# Net2CPC.net
KiCad netlist of a schematic drawn in EAGLE
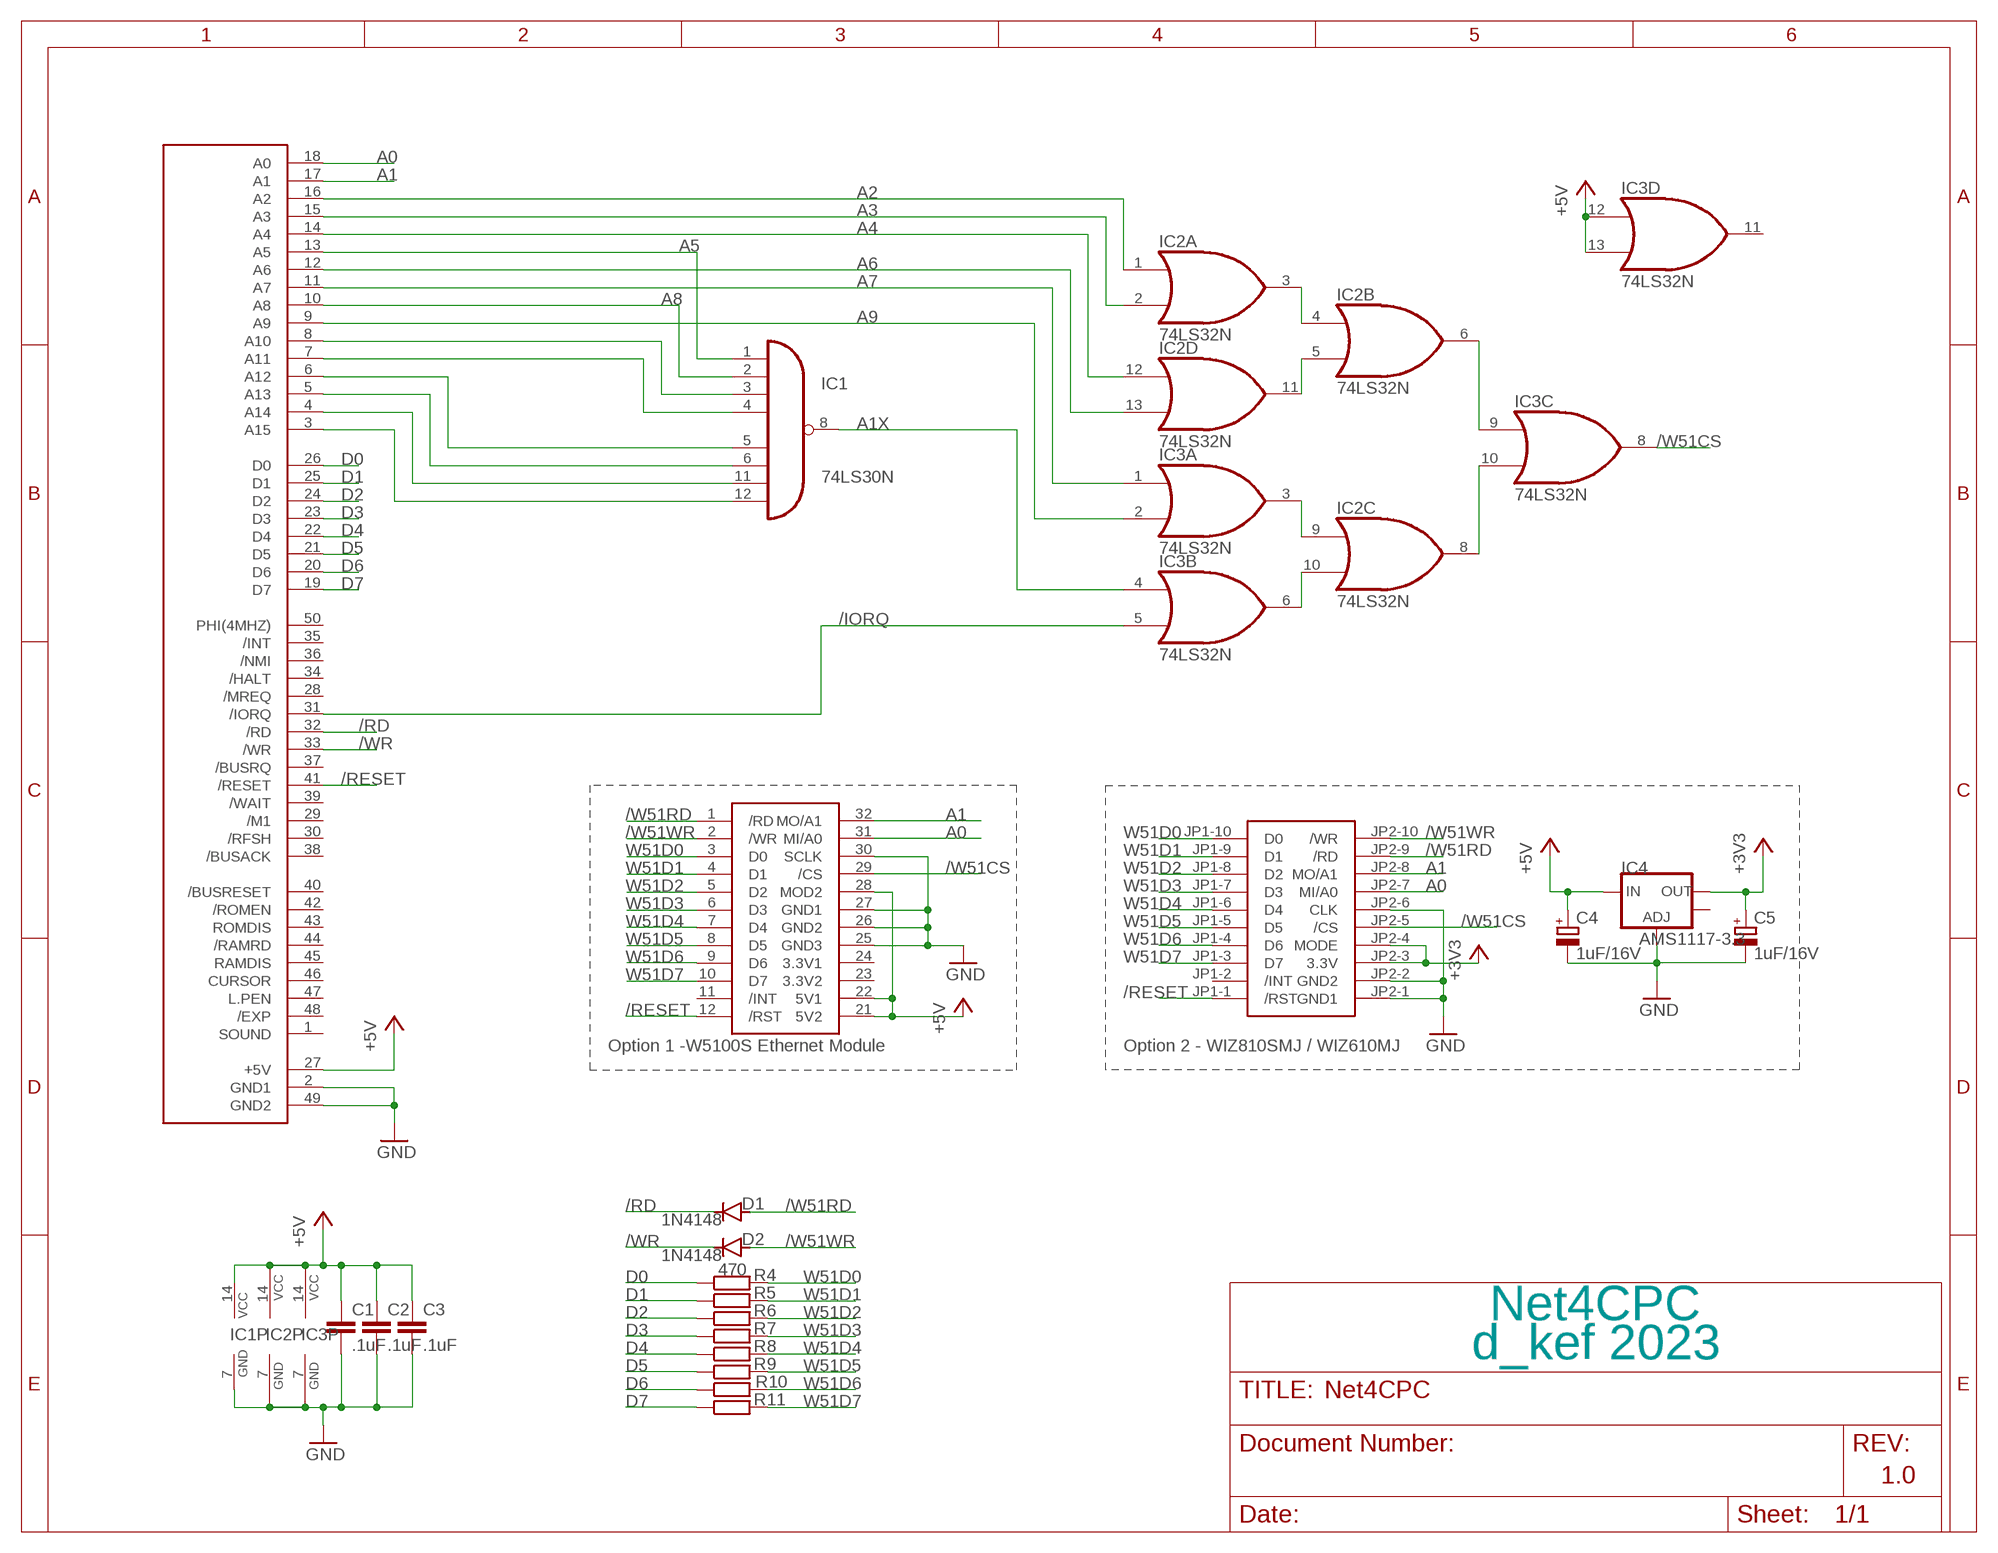
[diagram p0: schematic, sheet 1]

(export (version "E")
  (design (tool "Eeschema 10.0.6"))
  (components
    (comp (ref "C1")
      (value ".1uF")
      (footprint "eagle-import:C025-025X050")
      (libsource (lib "eagle-import") (part "C-EU025-025X050"))
    )
    (comp (ref "C2")
      (value ".1uF")
      (footprint "eagle-import:C025-025X050")
      (libsource (lib "eagle-import") (part "C-EU025-025X050"))
    )
    (comp (ref "C3")
      (value ".1uF")
      (footprint "eagle-import:C025-025X050")
      (libsource (lib "eagle-import") (part "C-EU025-025X050"))
    )
    (comp (ref "C4")
      (value "1uF/16V")
      (footprint "eagle-import:E5-6")
      (libsource (lib "eagle-import") (part "CPOL-EUE5-6"))
    )
    (comp (ref "C5")
      (value "1uF/16V")
      (footprint "eagle-import:E5-6")
      (libsource (lib "eagle-import") (part "CPOL-EUE5-6"))
    )
    (comp (ref "CON1")
      (value "CPCBUS")
      (footprint "eagle-import:2X25")
      (libsource (lib "eagle-import") (part "AMSTRAD_CPC_BUSP"))
    )
    (comp (ref "D1")
      (value "1N4148")
      (footprint "eagle-import:DO35-7")
      (libsource (lib "eagle-import") (part "1N4148DO35-7"))
    )
    (comp (ref "D2")
      (value "1N4148")
      (footprint "eagle-import:DO35-7")
      (libsource (lib "eagle-import") (part "1N4148DO35-7"))
    )
    (comp (ref "IC1")
      (value "74LS30N")
      (footprint "eagle-import:DIL14")
      (libsource (lib "eagle-import") (part "7430NHCT"))
    )
    (comp (ref "IC2")
      (value "74LS32N")
      (footprint "eagle-import:DIL14")
      (libsource (lib "eagle-import") (part "7432NLS"))
    )
    (comp (ref "IC3")
      (value "74LS32N")
      (footprint "eagle-import:DIL14")
      (libsource (lib "eagle-import") (part "7432NLS"))
    )
    (comp (ref "IC4")
      (value "AMS1117-3.3")
      (footprint "eagle-import:SOT223")
      (libsource (lib "eagle-import") (part "V_REG_LM1117SOT223"))
    )
    (comp (ref "R4")
      (value "470")
      (footprint "eagle-import:0204_7")
      (libsource (lib "eagle-import") (part "R-EU_0204/7"))
    )
    (comp (ref "R5")
      (value "470")
      (footprint "eagle-import:0204_7")
      (libsource (lib "eagle-import") (part "R-EU_0204/7"))
    )
    (comp (ref "R6")
      (value "470")
      (footprint "eagle-import:0204_7")
      (libsource (lib "eagle-import") (part "R-EU_0204/7"))
    )
    (comp (ref "R7")
      (value "470")
      (footprint "eagle-import:0204_7")
      (libsource (lib "eagle-import") (part "R-EU_0204/7"))
    )
    (comp (ref "R8")
      (value "470")
      (footprint "eagle-import:0204_7")
      (libsource (lib "eagle-import") (part "R-EU_0204/7"))
    )
    (comp (ref "R9")
      (value "470")
      (footprint "eagle-import:0204_7")
      (libsource (lib "eagle-import") (part "R-EU_0204/7"))
    )
    (comp (ref "R10")
      (value "470")
      (footprint "eagle-import:0204_7")
      (libsource (lib "eagle-import") (part "R-EU_0204/7"))
    )
    (comp (ref "R11")
      (value "470")
      (footprint "eagle-import:0204_7")
      (libsource (lib "eagle-import") (part "R-EU_0204/7"))
    )
    (comp (ref "W5100S-MODULE")
      (value "W5100S-NETWORK-MODULENO-NAMES")
      (footprint "eagle-import:W5100S-NETWORK-MODULE-NO-NAMES")
      (libsource (lib "eagle-import") (part "W5100S-NETWORK-MODULENO-NAMES"))
    )
    (comp (ref "WIZ810SMJ")
      (value "WIZ810SMJ-NETWORK-MODULENO-NAMES")
      (footprint "eagle-import:WIZ810SMJ-NETWORK-MODULE-NO-NAMES")
      (libsource (lib "eagle-import") (part "WIZ810SMJ-NETWORK-MODULENO-NAMES"))
    )
  )
  (nets
    (net (code "1") (name "+3V3") (class "Default")
      (node (ref "C5") (pin "+") (pinfunction "+_+") (pintype "passive"))
      (node (ref "IC4") (pin "2") (pinfunction "OUT_2") (pintype "output"))
      (node (ref "WIZ810SMJ") (pin "JP2-3") (pinfunction "3.3V_JP2-3") (pintype "power_in"))
      (node (ref "WIZ810SMJ") (pin "JP2-4") (pinfunction "MODE_JP2-4") (pintype "passive"))
    )
    (net (code "2") (name "+5V") (class "Default")
      (node (ref "C1") (pin "1") (pinfunction "1_1") (pintype "passive"))
      (node (ref "C2") (pin "1") (pinfunction "1_1") (pintype "passive"))
      (node (ref "C3") (pin "1") (pinfunction "1_1") (pintype "passive"))
      (node (ref "C4") (pin "+") (pinfunction "+_+") (pintype "passive"))
      (node (ref "CON1") (pin "27") (pinfunction "+5V_27") (pintype "bidirectional"))
      (node (ref "IC1") (pin "14") (pinfunction "VCC_14") (pintype "power_in"))
      (node (ref "IC2") (pin "14") (pinfunction "VCC_14") (pintype "power_in"))
      (node (ref "IC3") (pin "12") (pinfunction "I0_12") (pintype "input"))
      (node (ref "IC3") (pin "13") (pinfunction "I1_13") (pintype "input"))
      (node (ref "IC3") (pin "14") (pinfunction "VCC_14") (pintype "power_in"))
      (node (ref "IC4") (pin "3") (pinfunction "IN_3") (pintype "input"))
      (node (ref "W5100S-MODULE") (pin "21") (pinfunction "5V2_21") (pintype "power_in"))
      (node (ref "W5100S-MODULE") (pin "22") (pinfunction "5V1_22") (pintype "power_in"))
      (node (ref "W5100S-MODULE") (pin "28") (pinfunction "MOD2_28") (pintype "passive"))
    )
    (net (code "3") (name "/3.3V1") (class "Default")
      (node (ref "W5100S-MODULE") (pin "24") (pinfunction "3.3V1_24") (pintype "power_in"))
    )
    (net (code "4") (name "/3.3V2") (class "Default")
      (node (ref "W5100S-MODULE") (pin "23") (pinfunction "3.3V2_23") (pintype "power_in"))
    )
    (net (code "5") (name "/A0") (class "Default")
      (node (ref "CON1") (pin "18") (pinfunction "A0_18") (pintype "bidirectional"))
      (node (ref "W5100S-MODULE") (pin "31") (pinfunction "MI/A0_31") (pintype "input"))
      (node (ref "WIZ810SMJ") (pin "JP2-7") (pinfunction "MI/A0_JP2-7") (pintype "input"))
    )
    (net (code "6") (name "/A1") (class "Default")
      (node (ref "CON1") (pin "17") (pinfunction "A1_17") (pintype "bidirectional"))
      (node (ref "W5100S-MODULE") (pin "32") (pinfunction "MO/A1_32") (pintype "bidirectional"))
      (node (ref "WIZ810SMJ") (pin "JP2-8") (pinfunction "MO/A1_JP2-8") (pintype "bidirectional"))
    )
    (net (code "7") (name "/A1X") (class "Default")
      (node (ref "IC1") (pin "8") (pinfunction "O_8") (pintype "output"))
      (node (ref "IC3") (pin "4") (pinfunction "I0_4") (pintype "input"))
    )
    (net (code "8") (name "/A2") (class "Default")
      (node (ref "CON1") (pin "16") (pinfunction "A2_16") (pintype "bidirectional"))
      (node (ref "IC2") (pin "1") (pinfunction "I0_1") (pintype "input"))
    )
    (net (code "9") (name "/A3") (class "Default")
      (node (ref "CON1") (pin "15") (pinfunction "A3_15") (pintype "bidirectional"))
      (node (ref "IC2") (pin "2") (pinfunction "I1_2") (pintype "input"))
    )
    (net (code "10") (name "/A4") (class "Default")
      (node (ref "CON1") (pin "14") (pinfunction "A4_14") (pintype "bidirectional"))
      (node (ref "IC2") (pin "12") (pinfunction "I0_12") (pintype "input"))
    )
    (net (code "11") (name "/A5") (class "Default")
      (node (ref "CON1") (pin "13") (pinfunction "A5_13") (pintype "bidirectional"))
      (node (ref "IC1") (pin "1") (pinfunction "I0_1") (pintype "input"))
    )
    (net (code "12") (name "/A6") (class "Default")
      (node (ref "CON1") (pin "12") (pinfunction "A6_12") (pintype "bidirectional"))
      (node (ref "IC2") (pin "13") (pinfunction "I1_13") (pintype "input"))
    )
    (net (code "13") (name "/A7") (class "Default")
      (node (ref "CON1") (pin "11") (pinfunction "A7_11") (pintype "bidirectional"))
      (node (ref "IC3") (pin "1") (pinfunction "I0_1") (pintype "input"))
    )
    (net (code "14") (name "/A8") (class "Default")
      (node (ref "CON1") (pin "10") (pinfunction "A8_10") (pintype "bidirectional"))
      (node (ref "IC1") (pin "2") (pinfunction "I1_2") (pintype "input"))
    )
    (net (code "15") (name "/A9") (class "Default")
      (node (ref "CON1") (pin "9") (pinfunction "A9_9") (pintype "bidirectional"))
      (node (ref "IC3") (pin "2") (pinfunction "I1_2") (pintype "input"))
    )
    (net (code "16") (name "/D0") (class "Default")
      (node (ref "CON1") (pin "26") (pinfunction "D0_26") (pintype "bidirectional"))
      (node (ref "R4") (pin "1") (pinfunction "1_1") (pintype "passive"))
    )
    (net (code "17") (name "/D1") (class "Default")
      (node (ref "CON1") (pin "25") (pinfunction "D1_25") (pintype "bidirectional"))
      (node (ref "R5") (pin "1") (pinfunction "1_1") (pintype "passive"))
    )
    (net (code "18") (name "/D2") (class "Default")
      (node (ref "CON1") (pin "24") (pinfunction "D2_24") (pintype "bidirectional"))
      (node (ref "R6") (pin "1") (pinfunction "1_1") (pintype "passive"))
    )
    (net (code "19") (name "/D3") (class "Default")
      (node (ref "CON1") (pin "23") (pinfunction "D3_23") (pintype "bidirectional"))
      (node (ref "R7") (pin "1") (pinfunction "1_1") (pintype "passive"))
    )
    (net (code "20") (name "/D4") (class "Default")
      (node (ref "CON1") (pin "22") (pinfunction "D4_22") (pintype "bidirectional"))
      (node (ref "R8") (pin "1") (pinfunction "1_1") (pintype "passive"))
    )
    (net (code "21") (name "/D5") (class "Default")
      (node (ref "CON1") (pin "21") (pinfunction "D5_21") (pintype "bidirectional"))
      (node (ref "R9") (pin "1") (pinfunction "1_1") (pintype "passive"))
    )
    (net (code "22") (name "/D6") (class "Default")
      (node (ref "CON1") (pin "20") (pinfunction "D6_20") (pintype "bidirectional"))
      (node (ref "R10") (pin "1") (pinfunction "1_1") (pintype "passive"))
    )
    (net (code "23") (name "/D7") (class "Default")
      (node (ref "CON1") (pin "19") (pinfunction "D7_19") (pintype "bidirectional"))
      (node (ref "R11") (pin "1") (pinfunction "1_1") (pintype "passive"))
    )
    (net (code "24") (name "/W51D0") (class "Default")
      (node (ref "R4") (pin "2") (pinfunction "2_2") (pintype "passive"))
      (node (ref "W5100S-MODULE") (pin "3") (pinfunction "D0_3") (pintype "bidirectional"))
      (node (ref "WIZ810SMJ") (pin "JP1-10") (pinfunction "D0_JP1-10") (pintype "bidirectional"))
    )
    (net (code "25") (name "/W51D1") (class "Default")
      (node (ref "R5") (pin "2") (pinfunction "2_2") (pintype "passive"))
      (node (ref "W5100S-MODULE") (pin "4") (pinfunction "D1_4") (pintype "bidirectional"))
      (node (ref "WIZ810SMJ") (pin "JP1-9") (pinfunction "D1_JP1-9") (pintype "bidirectional"))
    )
    (net (code "26") (name "/W51D2") (class "Default")
      (node (ref "R6") (pin "2") (pinfunction "2_2") (pintype "passive"))
      (node (ref "W5100S-MODULE") (pin "5") (pinfunction "D2_5") (pintype "bidirectional"))
      (node (ref "WIZ810SMJ") (pin "JP1-8") (pinfunction "D2_JP1-8") (pintype "bidirectional"))
    )
    (net (code "27") (name "/W51D3") (class "Default")
      (node (ref "R7") (pin "2") (pinfunction "2_2") (pintype "passive"))
      (node (ref "W5100S-MODULE") (pin "6") (pinfunction "D3_6") (pintype "bidirectional"))
      (node (ref "WIZ810SMJ") (pin "JP1-7") (pinfunction "D3_JP1-7") (pintype "bidirectional"))
    )
    (net (code "28") (name "/W51D4") (class "Default")
      (node (ref "R8") (pin "2") (pinfunction "2_2") (pintype "passive"))
      (node (ref "W5100S-MODULE") (pin "7") (pinfunction "D4_7") (pintype "bidirectional"))
      (node (ref "WIZ810SMJ") (pin "JP1-6") (pinfunction "D4_JP1-6") (pintype "bidirectional"))
    )
    (net (code "29") (name "/W51D5") (class "Default")
      (node (ref "R9") (pin "2") (pinfunction "2_2") (pintype "passive"))
      (node (ref "W5100S-MODULE") (pin "8") (pinfunction "D5_8") (pintype "bidirectional"))
      (node (ref "WIZ810SMJ") (pin "JP1-5") (pinfunction "D5_JP1-5") (pintype "bidirectional"))
    )
    (net (code "30") (name "/W51D6") (class "Default")
      (node (ref "R10") (pin "2") (pinfunction "2_2") (pintype "passive"))
      (node (ref "W5100S-MODULE") (pin "9") (pinfunction "D6_9") (pintype "bidirectional"))
      (node (ref "WIZ810SMJ") (pin "JP1-4") (pinfunction "D6_JP1-4") (pintype "bidirectional"))
    )
    (net (code "31") (name "/W51D7") (class "Default")
      (node (ref "R11") (pin "2") (pinfunction "2_2") (pintype "passive"))
      (node (ref "W5100S-MODULE") (pin "10") (pinfunction "D7_10") (pintype "bidirectional"))
      (node (ref "WIZ810SMJ") (pin "JP1-3") (pinfunction "D7_JP1-3") (pintype "bidirectional"))
    )
    (net (code "32") (name "/{slash}IORQ") (class "Default")
      (node (ref "CON1") (pin "31") (pinfunction "/IORQ_31") (pintype "bidirectional"))
      (node (ref "IC3") (pin "5") (pinfunction "I1_5") (pintype "input"))
    )
    (net (code "33") (name "/{slash}RD") (class "Default")
      (node (ref "CON1") (pin "32") (pinfunction "/RD_32") (pintype "bidirectional"))
      (node (ref "D1") (pin "C") (pinfunction "C_C") (pintype "passive"))
    )
    (net (code "34") (name "/{slash}RESET") (class "Default")
      (node (ref "CON1") (pin "41") (pinfunction "/RESET_41") (pintype "bidirectional"))
      (node (ref "W5100S-MODULE") (pin "12") (pinfunction "/RST_12") (pintype "input"))
      (node (ref "WIZ810SMJ") (pin "JP1-1") (pinfunction "/RST_JP1-1") (pintype "input"))
    )
    (net (code "35") (name "/{slash}W51CS") (class "Default")
      (node (ref "IC3") (pin "8") (pinfunction "O_8") (pintype "output"))
      (node (ref "W5100S-MODULE") (pin "29") (pinfunction "/CS_29") (pintype "input"))
      (node (ref "WIZ810SMJ") (pin "JP2-5") (pinfunction "/CS_JP2-5") (pintype "input"))
    )
    (net (code "36") (name "/{slash}W51RD") (class "Default")
      (node (ref "D1") (pin "A") (pinfunction "A_A") (pintype "passive"))
      (node (ref "W5100S-MODULE") (pin "1") (pinfunction "/RD_1") (pintype "input"))
      (node (ref "WIZ810SMJ") (pin "JP2-9") (pinfunction "/RD_JP2-9") (pintype "input"))
    )
    (net (code "37") (name "/{slash}W51WR") (class "Default")
      (node (ref "D2") (pin "A") (pinfunction "A_A") (pintype "passive"))
      (node (ref "W5100S-MODULE") (pin "2") (pinfunction "/WR_2") (pintype "input"))
      (node (ref "WIZ810SMJ") (pin "JP2-10") (pinfunction "/WR_JP2-10") (pintype "input"))
    )
    (net (code "38") (name "/{slash}WR") (class "Default")
      (node (ref "CON1") (pin "33") (pinfunction "/WR_33") (pintype "bidirectional"))
      (node (ref "D2") (pin "C") (pinfunction "C_C") (pintype "passive"))
    )
    (net (code "39") (name "GND") (class "Default")
      (node (ref "C1") (pin "2") (pinfunction "2_2") (pintype "passive"))
      (node (ref "C2") (pin "2") (pinfunction "2_2") (pintype "passive"))
      (node (ref "C3") (pin "2") (pinfunction "2_2") (pintype "passive"))
      (node (ref "C4") (pin "-") (pinfunction "-_-") (pintype "passive"))
      (node (ref "C5") (pin "-") (pinfunction "-_-") (pintype "passive"))
      (node (ref "CON1") (pin "2") (pinfunction "GND1_2") (pintype "bidirectional"))
      (node (ref "CON1") (pin "49") (pinfunction "GND2_49") (pintype "bidirectional"))
      (node (ref "IC1") (pin "7") (pinfunction "GND_7") (pintype "power_in"))
      (node (ref "IC2") (pin "7") (pinfunction "GND_7") (pintype "power_in"))
      (node (ref "IC3") (pin "7") (pinfunction "GND_7") (pintype "power_in"))
      (node (ref "IC4") (pin "1") (pinfunction "ADJ_1") (pintype "input"))
      (node (ref "W5100S-MODULE") (pin "25") (pinfunction "GND3_25") (pintype "power_in"))
      (node (ref "W5100S-MODULE") (pin "26") (pinfunction "GND2_26") (pintype "power_in"))
      (node (ref "W5100S-MODULE") (pin "27") (pinfunction "GND1_27") (pintype "power_in"))
      (node (ref "W5100S-MODULE") (pin "30") (pinfunction "SCLK_30") (pintype "output"))
      (node (ref "WIZ810SMJ") (pin "JP2-1") (pinfunction "GND1_JP2-1") (pintype "power_in"))
      (node (ref "WIZ810SMJ") (pin "JP2-2") (pinfunction "GND2_JP2-2") (pintype "power_in"))
      (node (ref "WIZ810SMJ") (pin "JP2-6") (pinfunction "CLK_JP2-6") (pintype "output"))
    )
    (net (code "40") (name "Net-(CON1-A10)") (class "Default")
      (node (ref "CON1") (pin "8") (pinfunction "A10_8") (pintype "bidirectional"))
      (node (ref "IC1") (pin "3") (pinfunction "I2_3") (pintype "input"))
    )
    (net (code "41") (name "Net-(CON1-A11)") (class "Default")
      (node (ref "CON1") (pin "7") (pinfunction "A11_7") (pintype "bidirectional"))
      (node (ref "IC1") (pin "4") (pinfunction "I3_4") (pintype "input"))
    )
    (net (code "42") (name "Net-(CON1-A12)") (class "Default")
      (node (ref "CON1") (pin "6") (pinfunction "A12_6") (pintype "bidirectional"))
      (node (ref "IC1") (pin "5") (pinfunction "I4_5") (pintype "input"))
    )
    (net (code "43") (name "Net-(CON1-A13)") (class "Default")
      (node (ref "CON1") (pin "5") (pinfunction "A13_5") (pintype "bidirectional"))
      (node (ref "IC1") (pin "6") (pinfunction "I5_6") (pintype "input"))
    )
    (net (code "44") (name "Net-(CON1-A14)") (class "Default")
      (node (ref "CON1") (pin "4") (pinfunction "A14_4") (pintype "bidirectional"))
      (node (ref "IC1") (pin "11") (pinfunction "I6_11") (pintype "input"))
    )
    (net (code "45") (name "Net-(CON1-A15)") (class "Default")
      (node (ref "CON1") (pin "3") (pinfunction "A15_3") (pintype "bidirectional"))
      (node (ref "IC1") (pin "12") (pinfunction "I7_12") (pintype "input"))
    )
    (net (code "46") (name "Net-(IC2A-O)") (class "Default")
      (node (ref "IC2") (pin "3") (pinfunction "O_3") (pintype "output"))
      (node (ref "IC2") (pin "4") (pinfunction "I0_4") (pintype "input"))
    )
    (net (code "47") (name "Net-(IC2B-I1)") (class "Default")
      (node (ref "IC2") (pin "11") (pinfunction "O_11") (pintype "output"))
      (node (ref "IC2") (pin "5") (pinfunction "I1_5") (pintype "input"))
    )
    (net (code "48") (name "Net-(IC2B-O)") (class "Default")
      (node (ref "IC2") (pin "6") (pinfunction "O_6") (pintype "output"))
      (node (ref "IC3") (pin "9") (pinfunction "I0_9") (pintype "input"))
    )
    (net (code "49") (name "Net-(IC2C-I0)") (class "Default")
      (node (ref "IC2") (pin "9") (pinfunction "I0_9") (pintype "input"))
      (node (ref "IC3") (pin "3") (pinfunction "O_3") (pintype "output"))
    )
    (net (code "50") (name "Net-(IC2C-I1)") (class "Default")
      (node (ref "IC2") (pin "10") (pinfunction "I1_10") (pintype "input"))
      (node (ref "IC3") (pin "6") (pinfunction "O_6") (pintype "output"))
    )
    (net (code "51") (name "Net-(IC2C-O)") (class "Default")
      (node (ref "IC2") (pin "8") (pinfunction "O_8") (pintype "output"))
      (node (ref "IC3") (pin "10") (pinfunction "I1_10") (pintype "input"))
    )
    (net (code "52") (name "unconnected-(CON1-CURSOR-Pad46)") (class "Default")
      (node (ref "CON1") (pin "46") (pinfunction "CURSOR_46") (pintype "bidirectional"))
    )
    (net (code "53") (name "unconnected-(CON1-L.PEN-Pad47)") (class "Default")
      (node (ref "CON1") (pin "47") (pinfunction "L.PEN_47") (pintype "bidirectional"))
    )
    (net (code "54") (name "unconnected-(CON1-PHI(4MHZ)-Pad50)") (class "Default")
      (node (ref "CON1") (pin "50") (pinfunction "PHI(4MHZ)_50") (pintype "bidirectional"))
    )
    (net (code "55") (name "unconnected-(CON1-RAMDIS-Pad45)") (class "Default")
      (node (ref "CON1") (pin "45") (pinfunction "RAMDIS_45") (pintype "bidirectional"))
    )
    (net (code "56") (name "unconnected-(CON1-ROMDIS-Pad43)") (class "Default")
      (node (ref "CON1") (pin "43") (pinfunction "ROMDIS_43") (pintype "bidirectional"))
    )
    (net (code "57") (name "unconnected-(CON1-SOUND-Pad1)") (class "Default")
      (node (ref "CON1") (pin "1") (pinfunction "SOUND_1") (pintype "bidirectional"))
    )
    (net (code "58") (name "unconnected-(CON1-{slash}BUSACK-Pad38)") (class "Default")
      (node (ref "CON1") (pin "38") (pinfunction "/BUSACK_38") (pintype "bidirectional"))
    )
    (net (code "59") (name "unconnected-(CON1-{slash}BUSRESET-Pad40)") (class "Default")
      (node (ref "CON1") (pin "40") (pinfunction "/BUSRESET_40") (pintype "bidirectional"))
    )
    (net (code "60") (name "unconnected-(CON1-{slash}BUSRQ-Pad37)") (class "Default")
      (node (ref "CON1") (pin "37") (pinfunction "/BUSRQ_37") (pintype "bidirectional"))
    )
    (net (code "61") (name "unconnected-(CON1-{slash}EXP-Pad48)") (class "Default")
      (node (ref "CON1") (pin "48") (pinfunction "/EXP_48") (pintype "bidirectional"))
    )
    (net (code "62") (name "unconnected-(CON1-{slash}HALT-Pad34)") (class "Default")
      (node (ref "CON1") (pin "34") (pinfunction "/HALT_34") (pintype "bidirectional"))
    )
    (net (code "63") (name "unconnected-(CON1-{slash}INT-Pad35)") (class "Default")
      (node (ref "CON1") (pin "35") (pinfunction "/INT_35") (pintype "bidirectional"))
    )
    (net (code "64") (name "unconnected-(CON1-{slash}M1-Pad29)") (class "Default")
      (node (ref "CON1") (pin "29") (pinfunction "/M1_29") (pintype "bidirectional"))
    )
    (net (code "65") (name "unconnected-(CON1-{slash}MREQ-Pad28)") (class "Default")
      (node (ref "CON1") (pin "28") (pinfunction "/MREQ_28") (pintype "bidirectional"))
    )
    (net (code "66") (name "unconnected-(CON1-{slash}NMI-Pad36)") (class "Default")
      (node (ref "CON1") (pin "36") (pinfunction "/NMI_36") (pintype "bidirectional"))
    )
    (net (code "67") (name "unconnected-(CON1-{slash}RAMRD-Pad44)") (class "Default")
      (node (ref "CON1") (pin "44") (pinfunction "/RAMRD_44") (pintype "bidirectional"))
    )
    (net (code "68") (name "unconnected-(CON1-{slash}RFSH-Pad30)") (class "Default")
      (node (ref "CON1") (pin "30") (pinfunction "/RFSH_30") (pintype "bidirectional"))
    )
    (net (code "69") (name "unconnected-(CON1-{slash}ROMEN-Pad42)") (class "Default")
      (node (ref "CON1") (pin "42") (pinfunction "/ROMEN_42") (pintype "bidirectional"))
    )
    (net (code "70") (name "unconnected-(CON1-{slash}WAIT-Pad39)") (class "Default")
      (node (ref "CON1") (pin "39") (pinfunction "/WAIT_39") (pintype "bidirectional"))
    )
    (net (code "71") (name "unconnected-(IC3D-O-Pad11)") (class "Default")
      (node (ref "IC3") (pin "11") (pinfunction "O_11") (pintype "output"))
    )
    (net (code "72") (name "unconnected-(IC4-OUT-Pad4)") (class "Default")
      (node (ref "IC4") (pin "4") (pinfunction "OUT_4") (pintype "output"))
    )
    (net (code "73") (name "unconnected-(W5100S-MODULE-{slash}INT-Pad11)") (class "Default")
      (node (ref "W5100S-MODULE") (pin "11") (pinfunction "/INT_11") (pintype "output"))
    )
    (net (code "74") (name "unconnected-(WIZ810SMJ-{slash}INT-PadJP1-2)") (class "Default")
      (node (ref "WIZ810SMJ") (pin "JP1-2") (pinfunction "/INT_JP1-2") (pintype "output"))
    )
  )
)
